# Accelerometer.net
KiCad netlist of a schematic drawn in Altium Designer
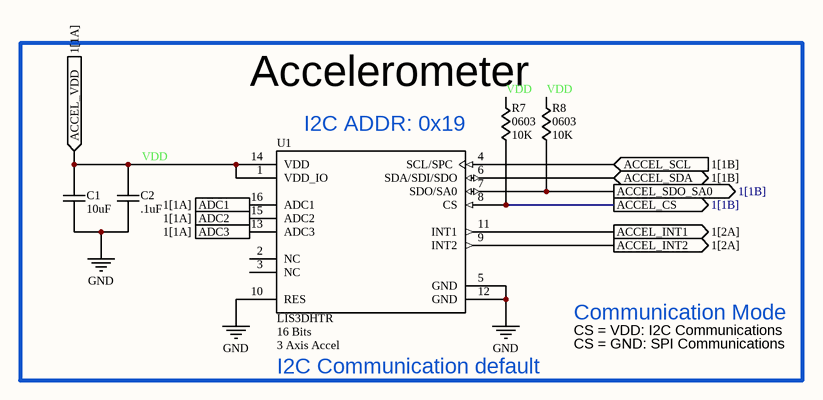
[diagram p0: Accelerometer.SchDoc]

(export (version "E")
  (design (tool "Eeschema 10.0.6"))
  (components
    (comp (ref "C1")
      (value "10uF")
      (footprint "PCB-CAP-SMD-0603")
      (description "Generic (no part number) 0603 surface mount capacitor")
      (fields (field (name "Comment") "CAP-SMD-0603"))
      (libsource (lib "Animal Inspired Movement and Robotics Lab (AIMRL)") (part "SCH-CAP-SMD-0603"))
    )
    (comp (ref "C2")
      (value ".1uF")
      (footprint "PCB-CAP-SMD-0603")
      (description "Generic (no part number) 0603 surface mount capacitor")
      (fields (field (name "Comment") "CAP-SMD-0603"))
      (libsource (lib "Animal Inspired Movement and Robotics Lab (AIMRL)") (part "SCH-CAP-SMD-0603"))
    )
    (comp (ref "R7")
      (value "10K")
      (footprint "0603")
      (description "Generic (no part number) 0603 surface mount resistor")
      (fields (field (name "Comment") "RES-SMD-0603"))
      (libsource (lib "Animal Inspired Movement and Robotics Lab (AIMRL)") (part "SCH-RES-SMD-0603"))
    )
    (comp (ref "R8")
      (value "10K")
      (footprint "0603")
      (description "Generic (no part number) 0603 surface mount resistor")
      (fields (field (name "Comment") "RES-SMD-0603"))
      (libsource (lib "Animal Inspired Movement and Robotics Lab (AIMRL)") (part "SCH-RES-SMD-0603"))
    )
    (comp (ref "U1")
      (value "SEN-ACCEL-16BIT-LIS3DHTR")
      (footprint "PCB-LGA16_3X3MM")
      (fields
        (field (name "RESOLUTION") "16 Bits")
        (field (name "PART NUMBER") "LIS3DHTR")
        (field (name "SENSOR TYPE") "3 Axis Accel")
      )
      (libsource (lib "Animal Inspired Movement and Robotics Lab (AIMRL)") (part "SCH-SEN-ACCEL-16BIT-LIS3DHTR"))
    )
  )
  (nets
    (net (code "1") (name "/ACCEL_CS") (class "Default")
      (node (ref "R7") (pin "1") (pinfunction "1_1") (pintype "passive"))
      (node (ref "U1") (pin "8") (pinfunction "CS_8") (pintype "input"))
    )
    (net (code "2") (name "/ACCEL_INT1") (class "Default")
      (node (ref "U1") (pin "11") (pinfunction "INT1_11") (pintype "output"))
    )
    (net (code "3") (name "/ACCEL_INT2") (class "Default")
      (node (ref "U1") (pin "9") (pinfunction "INT2_9") (pintype "output"))
    )
    (net (code "4") (name "/ACCEL_SCL") (class "Default")
      (node (ref "U1") (pin "4") (pinfunction "SCL/SPC_4") (pintype "input"))
    )
    (net (code "5") (name "/ACCEL_SDA") (class "Default")
      (node (ref "U1") (pin "6") (pinfunction "SDA/SDI/SDO_6") (pintype "bidirectional"))
    )
    (net (code "6") (name "/ACCEL_SDO_SA0") (class "Default")
      (node (ref "R8") (pin "1") (pinfunction "1_1") (pintype "passive"))
      (node (ref "U1") (pin "7") (pinfunction "SDO/SA0_7") (pintype "bidirectional"))
    )
    (net (code "7") (name "/ADC1") (class "Default")
      (node (ref "U1") (pin "16") (pinfunction "ADC1_16") (pintype "passive"))
    )
    (net (code "8") (name "/ADC2") (class "Default")
      (node (ref "U1") (pin "15") (pinfunction "ADC2_15") (pintype "passive"))
    )
    (net (code "9") (name "/ADC3") (class "Default")
      (node (ref "U1") (pin "13") (pinfunction "ADC3_13") (pintype "passive"))
    )
    (net (code "10") (name "/VDD") (class "Default")
      (node (ref "C1") (pin "1") (pinfunction "1_1") (pintype "passive"))
      (node (ref "C2") (pin "1") (pinfunction "1_1") (pintype "passive"))
      (node (ref "R7") (pin "2") (pinfunction "2_2") (pintype "passive"))
      (node (ref "R8") (pin "2") (pinfunction "2_2") (pintype "passive"))
      (node (ref "U1") (pin "1") (pinfunction "VDD_IO_1") (pintype "power_in"))
      (node (ref "U1") (pin "14") (pinfunction "VDD_14") (pintype "power_in"))
    )
    (net (code "11") (name "GND") (class "Default")
      (node (ref "C1") (pin "2") (pinfunction "2_2") (pintype "passive"))
      (node (ref "C2") (pin "2") (pinfunction "2_2") (pintype "passive"))
      (node (ref "U1") (pin "10") (pinfunction "RES_10") (pintype "passive"))
      (node (ref "U1") (pin "12") (pinfunction "GND_12") (pintype "power_in"))
      (node (ref "U1") (pin "5") (pinfunction "GND_5") (pintype "power_in"))
    )
    (net (code "12") (name "unconnected-(U1-NC-Pad2)") (class "Default")
      (node (ref "U1") (pin "2") (pinfunction "NC_2") (pintype "passive"))
    )
    (net (code "13") (name "unconnected-(U1-NC-Pad3)") (class "Default")
      (node (ref "U1") (pin "3") (pinfunction "NC_3") (pintype "passive"))
    )
  )
)
